# SensorStick.net
KiCad netlist of a schematic drawn in EAGLE
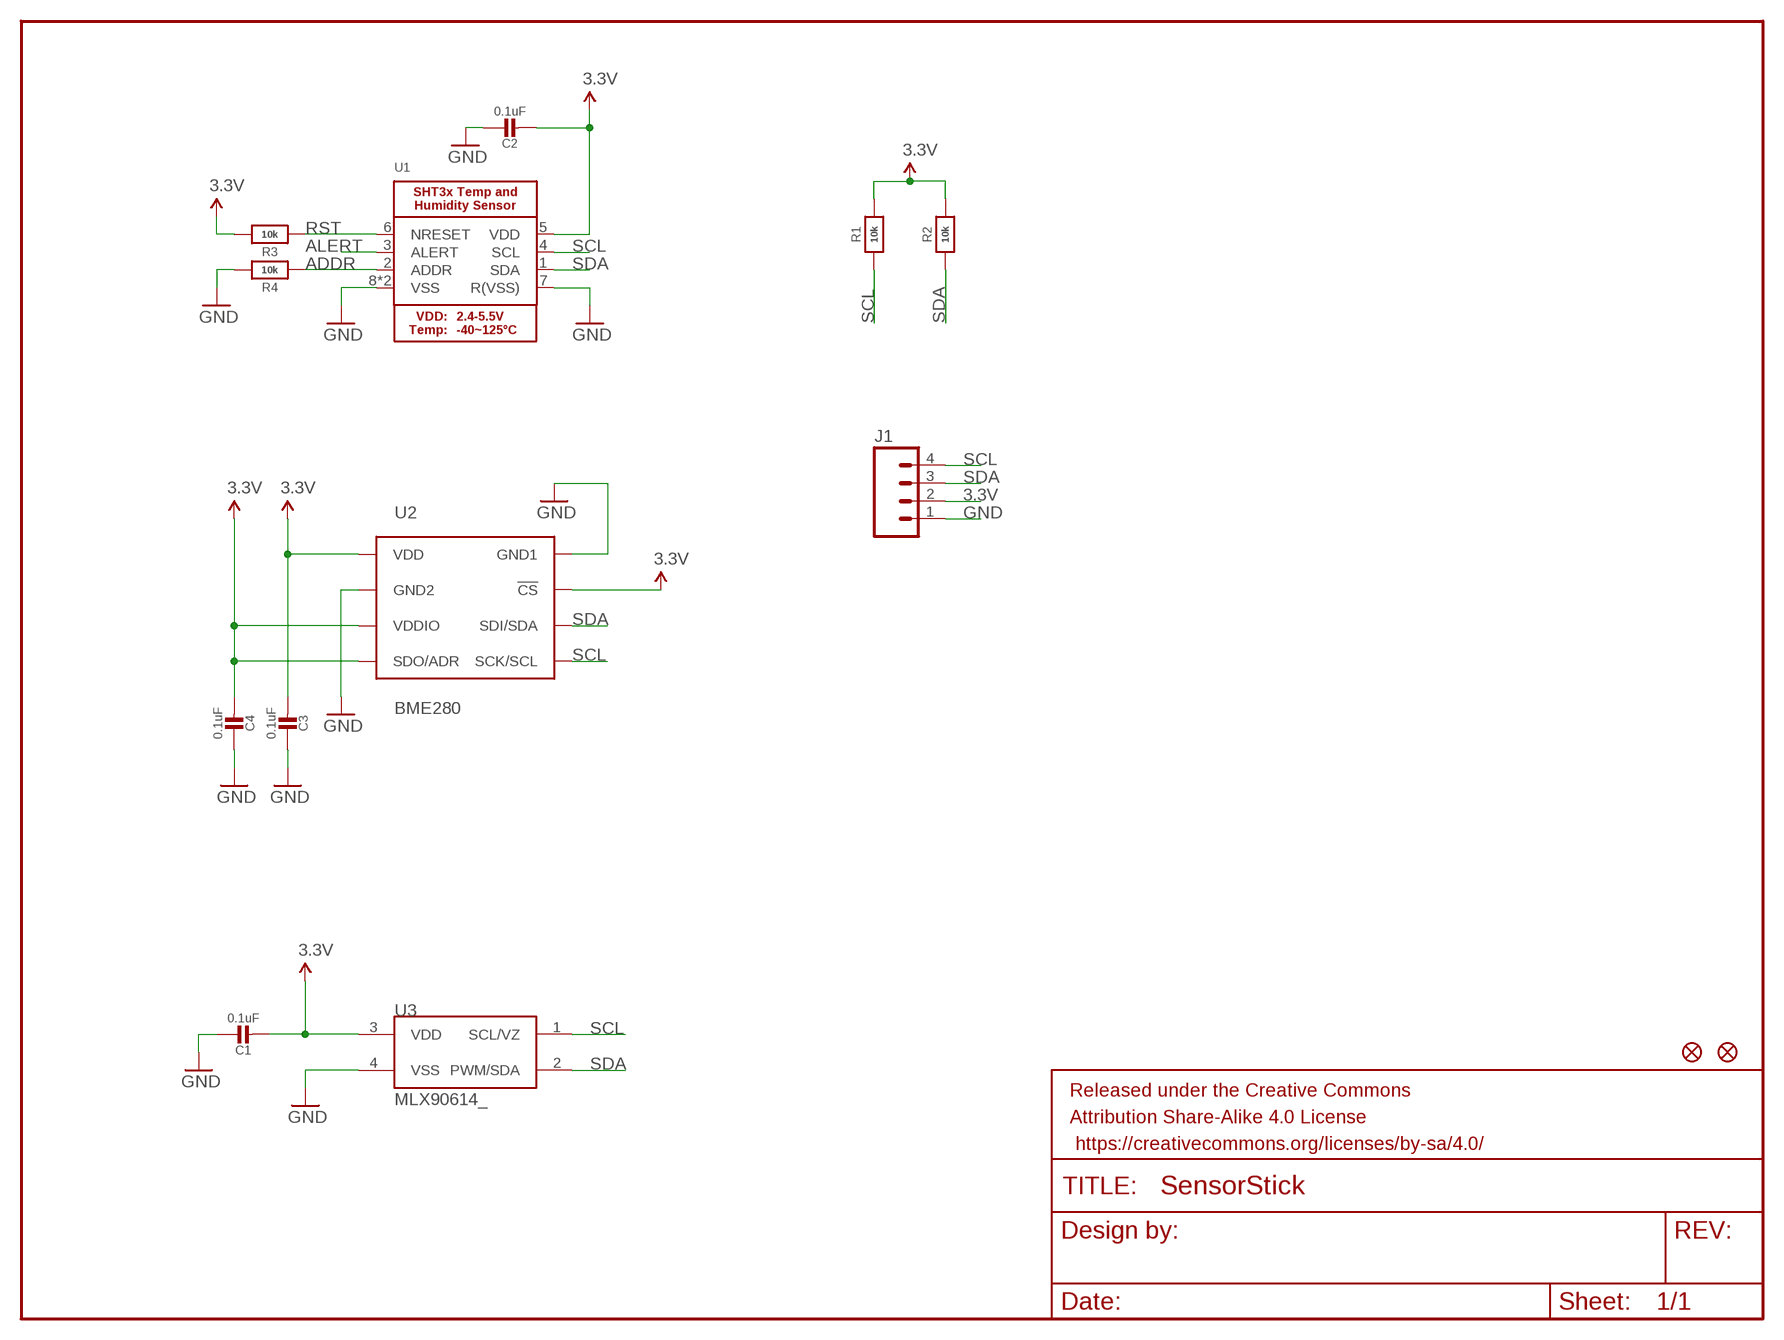
[diagram p0: schematic, sheet 1]

(export (version "E")
  (design (tool "Eeschema 10.0.6"))
  (components
    (comp (ref "C1")
      (value "0.1uF")
      (footprint "eagle-import:_0805")
      (libsource (lib "eagle-import") (part "CAP_CERAMIC_0805"))
    )
    (comp (ref "C2")
      (value "0.1uF")
      (footprint "eagle-import:_0805")
      (libsource (lib "eagle-import") (part "CAP_CERAMIC_0805"))
    )
    (comp (ref "C3")
      (value "0.1uF")
      (footprint "eagle-import:_0805")
      (libsource (lib "eagle-import") (part "CAP_CERAMIC_0805"))
    )
    (comp (ref "C4")
      (value "0.1uF")
      (footprint "eagle-import:_0805")
      (libsource (lib "eagle-import") (part "CAP_CERAMIC_0805"))
    )
    (comp (ref "FID1")
      (value "SPARKFUN-AESTHETICS_FIDUCIAL1X2")
      (footprint "eagle-import:SPARKFUN-AESTHETICS_FIDUCIAL-1X2")
      (libsource (lib "eagle-import") (part "SPARKFUN-AESTHETICS_FIDUCIAL1X2"))
    )
    (comp (ref "FID2")
      (value "SPARKFUN-AESTHETICS_FIDUCIAL1X2")
      (footprint "eagle-import:SPARKFUN-AESTHETICS_FIDUCIAL-1X2")
      (libsource (lib "eagle-import") (part "SPARKFUN-AESTHETICS_FIDUCIAL1X2"))
    )
    (comp (ref "FRAME1")
      (value "FRAME-LETTERNO_PACKAGE")
      (footprint "eagle-import:DUMMY")
      (fields (field (name "DESIGNER") "Nobody"))
      (libsource (lib "eagle-import") (part "FRAME-LETTERNO_PACKAGE"))
    )
    (comp (ref "J1")
      (value "M04PTH")
      (footprint "eagle-import:1X04")
      (libsource (lib "eagle-import") (part "M04PTH"))
    )
    (comp (ref "R1")
      (value "10k")
      (footprint "eagle-import:_0805")
      (libsource (lib "eagle-import") (part "RESISTOR_0805"))
    )
    (comp (ref "R2")
      (value "10k")
      (footprint "eagle-import:_0805")
      (libsource (lib "eagle-import") (part "RESISTOR_0805"))
    )
    (comp (ref "R3")
      (value "10k")
      (footprint "eagle-import:_0805")
      (libsource (lib "eagle-import") (part "RESISTOR_0805"))
    )
    (comp (ref "R4")
      (value "10k")
      (footprint "eagle-import:_0805")
      (libsource (lib "eagle-import") (part "RESISTOR_0805"))
    )
    (comp (ref "U1")
      (value "SHT3X")
      (footprint "eagle-import:SHT3X")
      (libsource (lib "eagle-import") (part "SHT3X"))
    )
    (comp (ref "U2")
      (value "BME280")
      (footprint "eagle-import:BME280COMPONENTLIBRARY_BME280_LGA")
      (libsource (lib "eagle-import") (part "BME280COMPONENTLIBRARY_BME280"))
    )
    (comp (ref "U3")
      (value "MLX90614_")
      (footprint "eagle-import:TO-39")
      (libsource (lib "eagle-import") (part "MLX90614_"))
    )
  )
  (nets
    (net (code "1") (name "/ADDR") (class "Default")
      (node (ref "R4") (pin "1") (pinfunction "1_1") (pintype "passive"))
      (node (ref "U1") (pin "2") (pinfunction "ADDR_2") (pintype "bidirectional"))
    )
    (net (code "2") (name "/ALERT") (class "Default")
      (node (ref "U1") (pin "3") (pinfunction "ALERT_3") (pintype "bidirectional"))
    )
    (net (code "3") (name "/RST") (class "Default")
      (node (ref "R3") (pin "1") (pinfunction "1_1") (pintype "passive"))
      (node (ref "U1") (pin "6") (pinfunction "NRESET_6") (pintype "bidirectional"))
    )
    (net (code "4") (name "/SCL") (class "Default")
      (node (ref "J1") (pin "4") (pinfunction "4_4") (pintype "passive"))
      (node (ref "R1") (pin "1") (pinfunction "1_1") (pintype "passive"))
      (node (ref "U1") (pin "4") (pinfunction "SCL_4") (pintype "bidirectional"))
      (node (ref "U2") (pin "P$4") (pinfunction "SCK/SCL_P$4") (pintype "bidirectional"))
      (node (ref "U3") (pin "1") (pinfunction "SCL/VZ_1") (pintype "bidirectional"))
    )
    (net (code "5") (name "/SDA") (class "Default")
      (node (ref "J1") (pin "3") (pinfunction "3_3") (pintype "passive"))
      (node (ref "R2") (pin "1") (pinfunction "1_1") (pintype "passive"))
      (node (ref "U1") (pin "1") (pinfunction "SDA_1") (pintype "bidirectional"))
      (node (ref "U2") (pin "P$3") (pinfunction "SDI/SDA_P$3") (pintype "bidirectional"))
      (node (ref "U3") (pin "2") (pinfunction "PWM/SDA_2") (pintype "bidirectional"))
    )
    (net (code "6") (name "3.3V") (class "Default")
      (node (ref "C1") (pin "2") (pinfunction "2_2") (pintype "passive"))
      (node (ref "C2") (pin "2") (pinfunction "2_2") (pintype "passive"))
      (node (ref "C3") (pin "2") (pinfunction "2_2") (pintype "passive"))
      (node (ref "C4") (pin "2") (pinfunction "2_2") (pintype "passive"))
      (node (ref "J1") (pin "2") (pinfunction "2_2") (pintype "passive"))
      (node (ref "R1") (pin "2") (pinfunction "2_2") (pintype "passive"))
      (node (ref "R2") (pin "2") (pinfunction "2_2") (pintype "passive"))
      (node (ref "R3") (pin "2") (pinfunction "2_2") (pintype "passive"))
      (node (ref "U1") (pin "5") (pinfunction "VDD_5") (pintype "power_in"))
      (node (ref "U2") (pin "P$2") (pinfunction "~{CS}_P$2") (pintype "bidirectional"))
      (node (ref "U2") (pin "P$5") (pinfunction "SDO/ADR_P$5") (pintype "bidirectional"))
      (node (ref "U2") (pin "P$6") (pinfunction "VDDIO_P$6") (pintype "bidirectional"))
      (node (ref "U2") (pin "P$8") (pinfunction "VDD_P$8") (pintype "bidirectional"))
      (node (ref "U3") (pin "3") (pinfunction "VDD_3") (pintype "bidirectional"))
    )
    (net (code "7") (name "GND") (class "Default")
      (node (ref "C1") (pin "1") (pinfunction "1_1") (pintype "passive"))
      (node (ref "C2") (pin "1") (pinfunction "1_1") (pintype "passive"))
      (node (ref "C3") (pin "1") (pinfunction "1_1") (pintype "passive"))
      (node (ref "C4") (pin "1") (pinfunction "1_1") (pintype "passive"))
      (node (ref "J1") (pin "1") (pinfunction "1_1") (pintype "passive"))
      (node (ref "R4") (pin "2") (pinfunction "2_2") (pintype "passive"))
      (node (ref "U1") (pin "7") (pinfunction "R(VSS)_7") (pintype "bidirectional"))
      (node (ref "U1") (pin "8") (pinfunction "VSS_8") (pintype "power_in"))
      (node (ref "U1") (pin "THERMAL") (pinfunction "VSS_THERMAL") (pintype "power_in"))
      (node (ref "U2") (pin "P$1") (pinfunction "GND1_P$1") (pintype "bidirectional"))
      (node (ref "U2") (pin "P$7") (pinfunction "GND2_P$7") (pintype "bidirectional"))
      (node (ref "U3") (pin "4") (pinfunction "VSS_4") (pintype "bidirectional"))
    )
  )
)
